# ionode.net
KiCad netlist of a schematic drawn in EAGLE
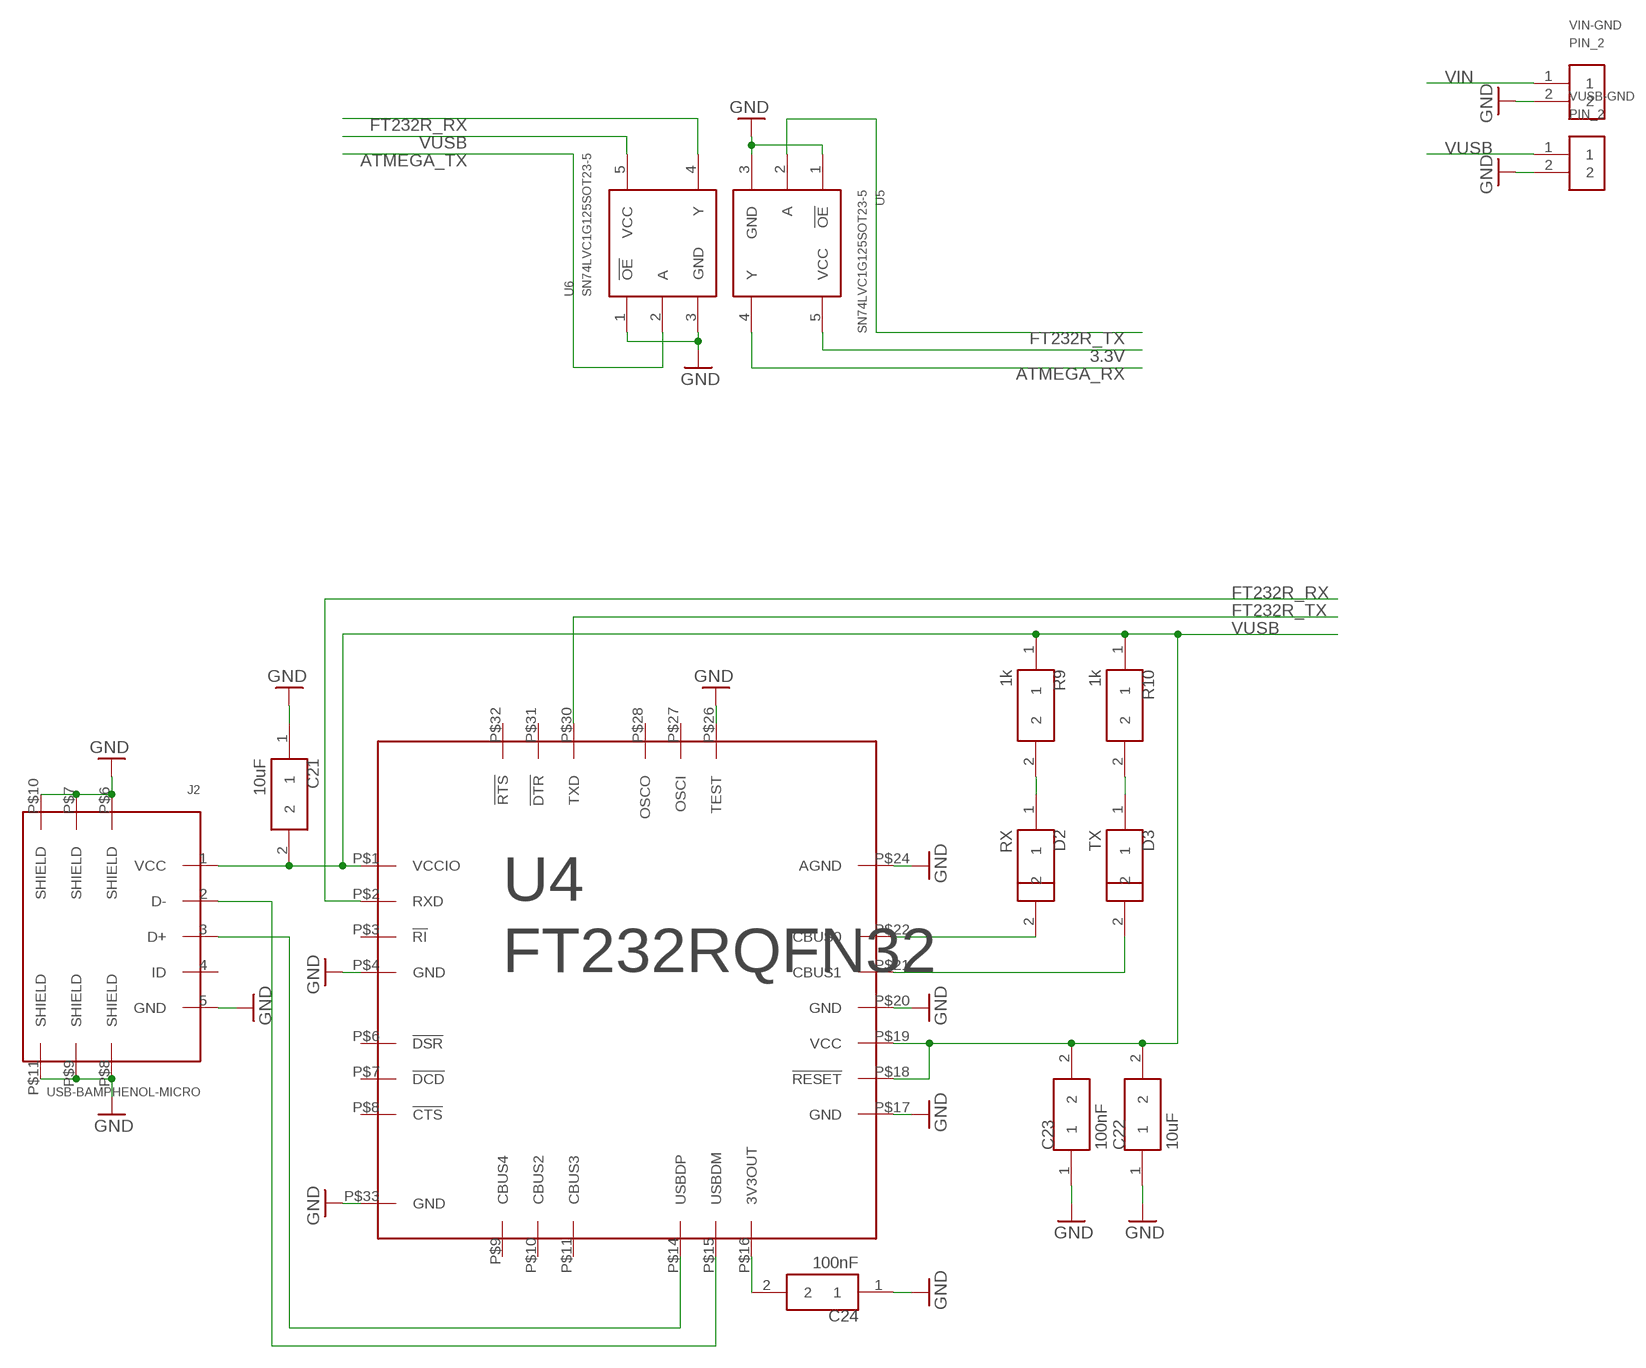
[diagram p0: schematic, sheet 1, part 1 of 2]
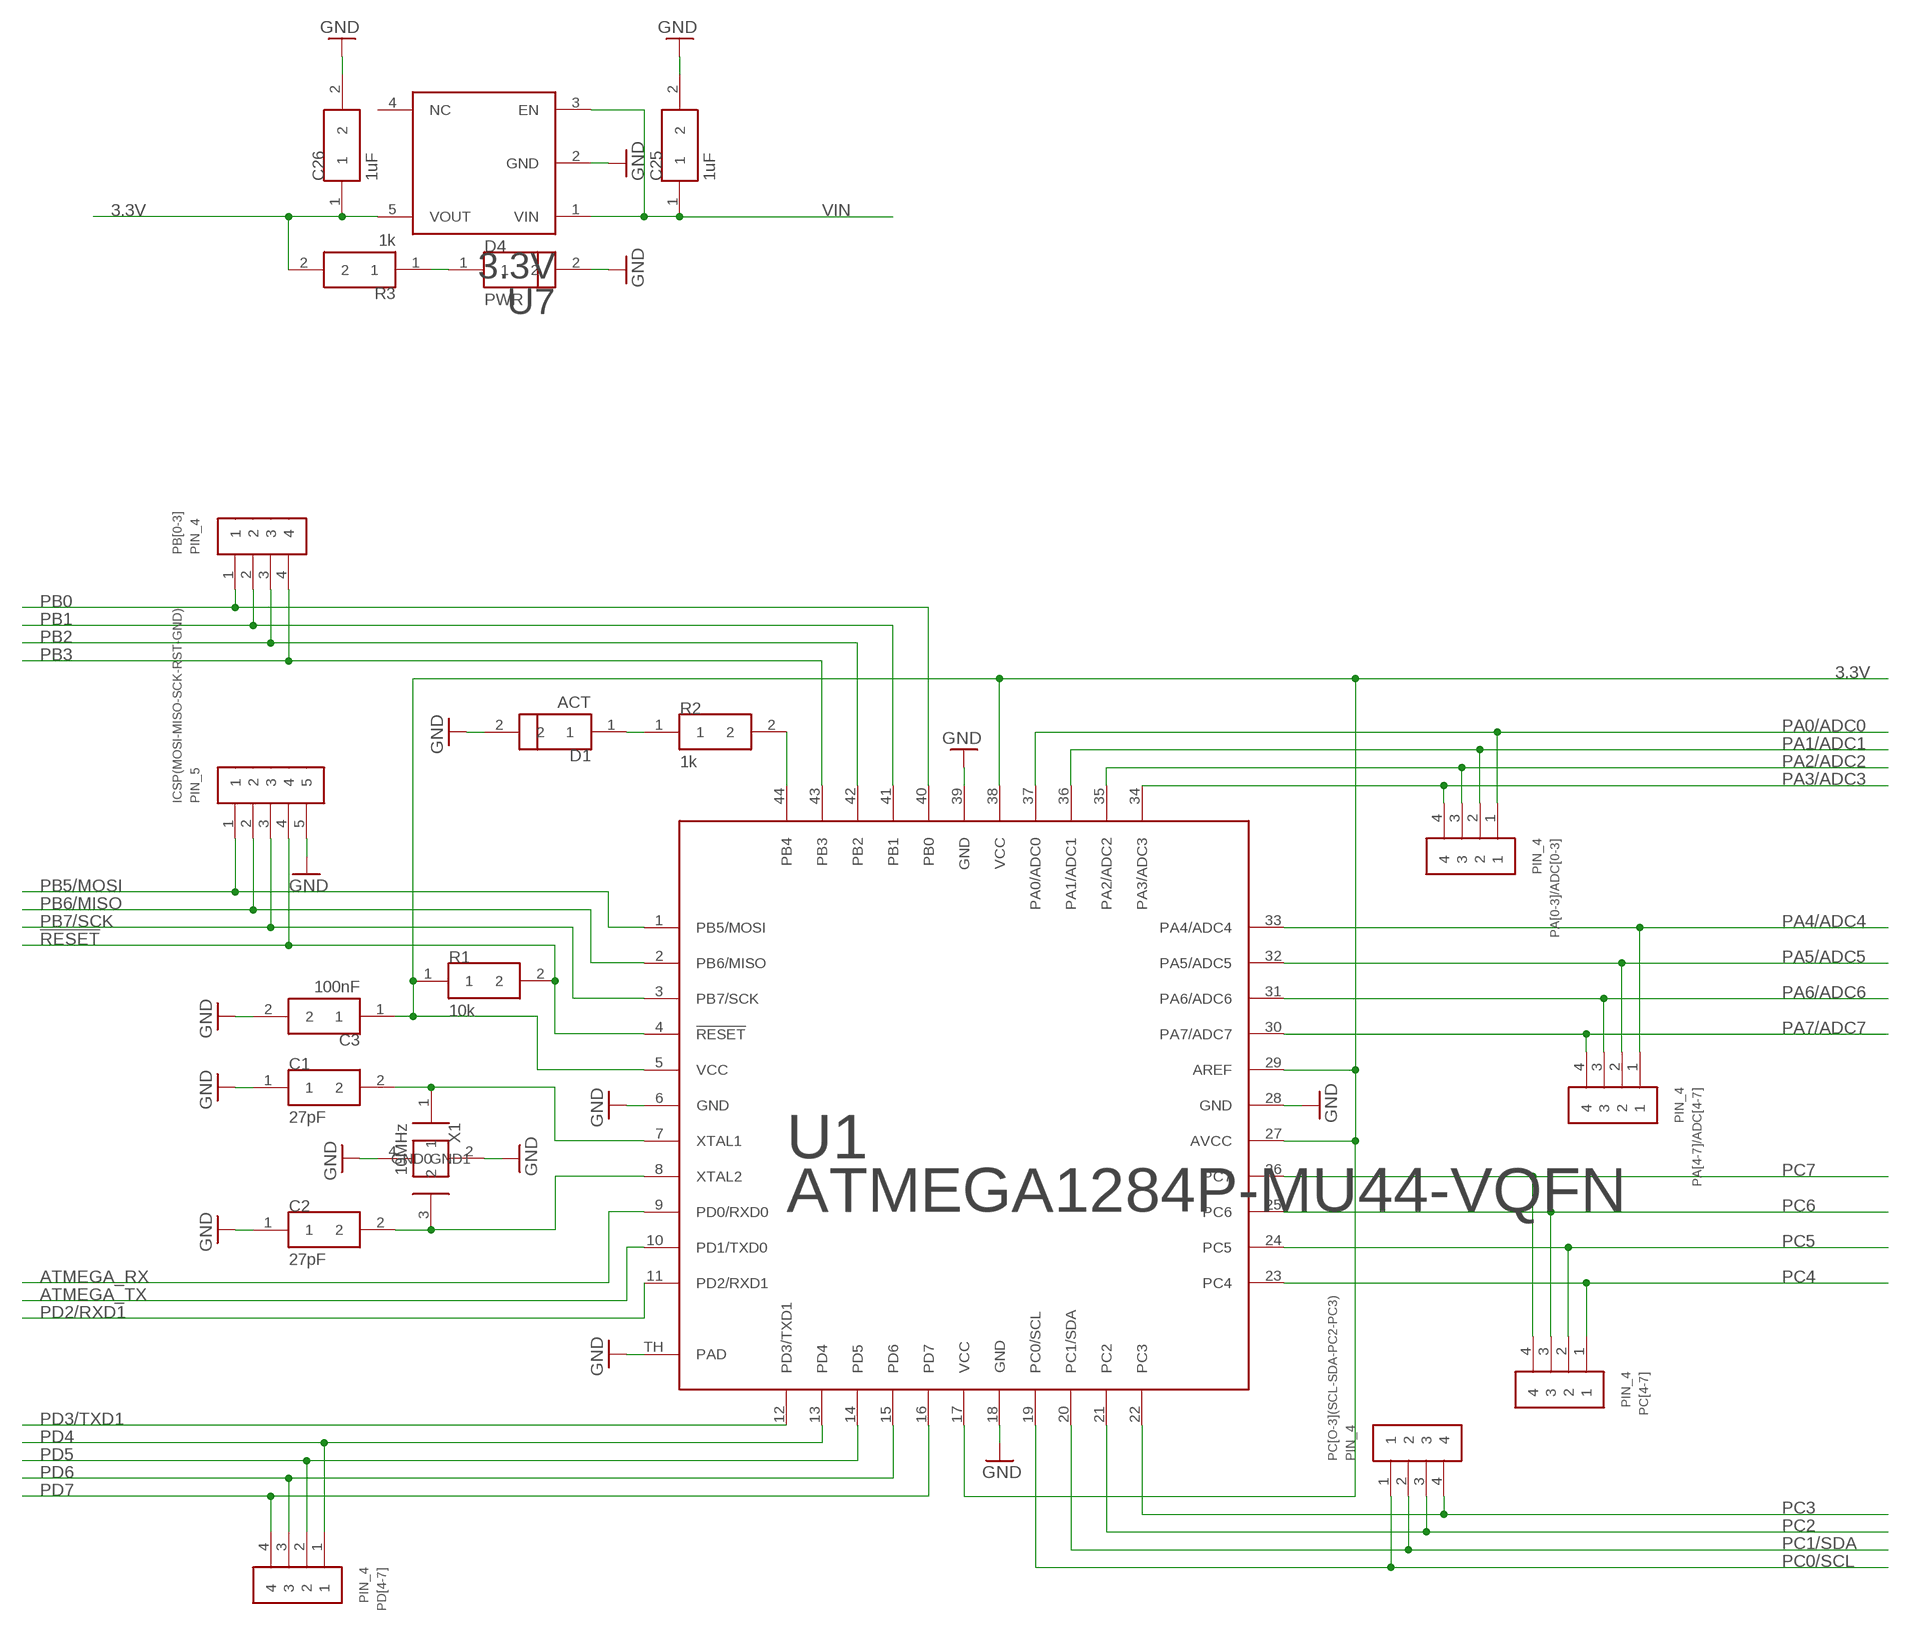
[diagram p1: schematic, sheet 1, part 2 of 2]

(export (version "E")
  (design (tool "Eeschema 10.0.6"))
  (components
    (comp (ref "C1")
      (value "27pF")
      (footprint "eagle-import:0805")
      (libsource (lib "eagle-import") (part "CAP0805"))
    )
    (comp (ref "C2")
      (value "27pF")
      (footprint "eagle-import:0805")
      (libsource (lib "eagle-import") (part "CAP0805"))
    )
    (comp (ref "C3")
      (value "100nF")
      (footprint "eagle-import:0805")
      (libsource (lib "eagle-import") (part "CAP0805"))
    )
    (comp (ref "C21")
      (value "10uF")
      (footprint "eagle-import:0805")
      (libsource (lib "eagle-import") (part "CAP0805"))
    )
    (comp (ref "C22")
      (value "10uF")
      (footprint "eagle-import:0805")
      (libsource (lib "eagle-import") (part "CAP0805"))
    )
    (comp (ref "C23")
      (value "100nF")
      (footprint "eagle-import:0805")
      (libsource (lib "eagle-import") (part "CAP0805"))
    )
    (comp (ref "C24")
      (value "100nF")
      (footprint "eagle-import:0805")
      (libsource (lib "eagle-import") (part "CAP0805"))
    )
    (comp (ref "C25")
      (value "1uF")
      (footprint "eagle-import:0805")
      (libsource (lib "eagle-import") (part "CAP0805"))
    )
    (comp (ref "C26")
      (value "1uF")
      (footprint "eagle-import:0805")
      (libsource (lib "eagle-import") (part "CAP0805"))
    )
    (comp (ref "D1")
      (value "ACT")
      (footprint "eagle-import:0805")
      (libsource (lib "eagle-import") (part "LED0805"))
    )
    (comp (ref "D2")
      (value "RX")
      (footprint "eagle-import:0805")
      (libsource (lib "eagle-import") (part "LED0805"))
    )
    (comp (ref "D3")
      (value "TX")
      (footprint "eagle-import:0805")
      (libsource (lib "eagle-import") (part "LED0805"))
    )
    (comp (ref "D4")
      (value "PWR")
      (footprint "eagle-import:0805")
      (libsource (lib "eagle-import") (part "LED0805"))
    )
    (comp (ref "ICSP(MOSI-MISO-SCK-RST-GND)")
      (value "PIN_5")
      (footprint "eagle-import:PIN_5")
      (libsource (lib "eagle-import") (part "PIN_5"))
    )
    (comp (ref "J2")
      (value "USB-BAMPHENOL-MICRO")
      (footprint "eagle-import:AMPHENOL-USB-MICRO-B")
      (libsource (lib "eagle-import") (part "USB-BAMPHENOL-MICRO"))
    )
    (comp (ref "PA[0-3]/ADC[0-3]")
      (value "PIN_4")
      (footprint "eagle-import:PIN_4")
      (libsource (lib "eagle-import") (part "PIN_4"))
    )
    (comp (ref "PA[4-7]/ADC[4-7]")
      (value "PIN_4")
      (footprint "eagle-import:PIN_4")
      (libsource (lib "eagle-import") (part "PIN_4"))
    )
    (comp (ref "PB[0-3]")
      (value "PIN_4")
      (footprint "eagle-import:PIN_4")
      (libsource (lib "eagle-import") (part "PIN_4"))
    )
    (comp (ref "PC[4-7]")
      (value "PIN_4")
      (footprint "eagle-import:PIN_4")
      (libsource (lib "eagle-import") (part "PIN_4"))
    )
    (comp (ref "PC[O-3](SCL-SDA-PC2-PC3)")
      (value "PIN_4")
      (footprint "eagle-import:PIN_4")
      (libsource (lib "eagle-import") (part "PIN_4"))
    )
    (comp (ref "PD[4-7]")
      (value "PIN_4")
      (footprint "eagle-import:PIN_4")
      (libsource (lib "eagle-import") (part "PIN_4"))
    )
    (comp (ref "R1")
      (value "10k")
      (footprint "eagle-import:0805")
      (libsource (lib "eagle-import") (part "RES0805"))
    )
    (comp (ref "R2")
      (value "1k")
      (footprint "eagle-import:0805")
      (libsource (lib "eagle-import") (part "RES0805"))
    )
    (comp (ref "R3")
      (value "1k")
      (footprint "eagle-import:0805")
      (libsource (lib "eagle-import") (part "RES0805"))
    )
    (comp (ref "R9")
      (value "1k")
      (footprint "eagle-import:0805")
      (libsource (lib "eagle-import") (part "RES0805"))
    )
    (comp (ref "R10")
      (value "1k")
      (footprint "eagle-import:0805")
      (libsource (lib "eagle-import") (part "RES0805"))
    )
    (comp (ref "U1")
      (value "ATMEGA1284P-MU44-VQFN")
      (footprint "eagle-import:44-VQFN")
      (libsource (lib "eagle-import") (part "ATMEGA1284P-MU44-VQFN"))
    )
    (comp (ref "U4")
      (value "FT232RQFN32")
      (footprint "eagle-import:32-VQFN")
      (libsource (lib "eagle-import") (part "FT232RQFN32"))
    )
    (comp (ref "U5")
      (value "SN74LVC1G125SOT23-5")
      (footprint "eagle-import:SOT23-5")
      (libsource (lib "eagle-import") (part "SN74LVC1G125SOT23-5"))
    )
    (comp (ref "U6")
      (value "SN74LVC1G125SOT23-5")
      (footprint "eagle-import:SOT23-5")
      (libsource (lib "eagle-import") (part "SN74LVC1G125SOT23-5"))
    )
    (comp (ref "U7")
      (value "3.3V")
      (footprint "eagle-import:SOT23-5")
      (libsource (lib "eagle-import") (part "LP3985SOT23-5"))
    )
    (comp (ref "VIN-GND")
      (value "PIN_2")
      (footprint "eagle-import:PIN_2")
      (libsource (lib "eagle-import") (part "PIN_2"))
    )
    (comp (ref "VUSB-GND")
      (value "PIN_2")
      (footprint "eagle-import:PIN_2")
      (libsource (lib "eagle-import") (part "PIN_2"))
    )
    (comp (ref "X1")
      (value "10MHz")
      (footprint "eagle-import:XTAL_3225")
      (libsource (lib "eagle-import") (part "XTAL_GNDSMD_3225"))
    )
  )
  (nets
    (net (code "1") (name "/3.3V") (class "Default")
      (node (ref "C26") (pin "1") (pinfunction "1_1") (pintype "bidirectional"))
      (node (ref "C3") (pin "1") (pinfunction "1_1") (pintype "bidirectional"))
      (node (ref "R1") (pin "1") (pinfunction "1_1") (pintype "bidirectional"))
      (node (ref "R3") (pin "2") (pinfunction "2_2") (pintype "bidirectional"))
      (node (ref "U1") (pin "17") (pinfunction "VCC_17") (pintype "bidirectional"))
      (node (ref "U1") (pin "27") (pinfunction "AVCC_27") (pintype "bidirectional"))
      (node (ref "U1") (pin "29") (pinfunction "AREF_29") (pintype "bidirectional"))
      (node (ref "U1") (pin "38") (pinfunction "VCC_38") (pintype "bidirectional"))
      (node (ref "U1") (pin "5") (pinfunction "VCC_5") (pintype "bidirectional"))
      (node (ref "U5") (pin "5") (pinfunction "VCC_5") (pintype "bidirectional"))
      (node (ref "U7") (pin "5") (pinfunction "VOUT_5") (pintype "bidirectional"))
    )
    (net (code "2") (name "/ATMEGA_RX") (class "Default")
      (node (ref "U1") (pin "9") (pinfunction "PD0/RXD0_9") (pintype "bidirectional"))
      (node (ref "U5") (pin "4") (pinfunction "Y_4") (pintype "bidirectional"))
    )
    (net (code "3") (name "/ATMEGA_TX") (class "Default")
      (node (ref "U1") (pin "10") (pinfunction "PD1/TXD0_10") (pintype "bidirectional"))
      (node (ref "U6") (pin "2") (pinfunction "A_2") (pintype "bidirectional"))
    )
    (net (code "4") (name "/FT232R_RX") (class "Default")
      (node (ref "U4") (pin "P$2") (pinfunction "RXD_P$2") (pintype "bidirectional"))
      (node (ref "U6") (pin "4") (pinfunction "Y_4") (pintype "bidirectional"))
    )
    (net (code "5") (name "/FT232R_TX") (class "Default")
      (node (ref "U4") (pin "P$30") (pinfunction "TXD_P$30") (pintype "bidirectional"))
      (node (ref "U5") (pin "2") (pinfunction "A_2") (pintype "bidirectional"))
    )
    (net (code "6") (name "/PA0{slash}ADC0") (class "Default")
      (node (ref "PA[0-3]/ADC[0-3]") (pin "1") (pinfunction "1_1") (pintype "bidirectional"))
      (node (ref "U1") (pin "37") (pinfunction "PA0/ADC0_37") (pintype "bidirectional"))
    )
    (net (code "7") (name "/PA1{slash}ADC1") (class "Default")
      (node (ref "PA[0-3]/ADC[0-3]") (pin "2") (pinfunction "2_2") (pintype "bidirectional"))
      (node (ref "U1") (pin "36") (pinfunction "PA1/ADC1_36") (pintype "bidirectional"))
    )
    (net (code "8") (name "/PA2{slash}ADC2") (class "Default")
      (node (ref "PA[0-3]/ADC[0-3]") (pin "3") (pinfunction "3_3") (pintype "bidirectional"))
      (node (ref "U1") (pin "35") (pinfunction "PA2/ADC2_35") (pintype "bidirectional"))
    )
    (net (code "9") (name "/PA3{slash}ADC3") (class "Default")
      (node (ref "PA[0-3]/ADC[0-3]") (pin "4") (pinfunction "4_4") (pintype "bidirectional"))
      (node (ref "U1") (pin "34") (pinfunction "PA3/ADC3_34") (pintype "bidirectional"))
    )
    (net (code "10") (name "/PA4{slash}ADC4") (class "Default")
      (node (ref "PA[4-7]/ADC[4-7]") (pin "1") (pinfunction "1_1") (pintype "bidirectional"))
      (node (ref "U1") (pin "33") (pinfunction "PA4/ADC4_33") (pintype "bidirectional"))
    )
    (net (code "11") (name "/PA5{slash}ADC5") (class "Default")
      (node (ref "PA[4-7]/ADC[4-7]") (pin "2") (pinfunction "2_2") (pintype "bidirectional"))
      (node (ref "U1") (pin "32") (pinfunction "PA5/ADC5_32") (pintype "bidirectional"))
    )
    (net (code "12") (name "/PA6{slash}ADC6") (class "Default")
      (node (ref "PA[4-7]/ADC[4-7]") (pin "3") (pinfunction "3_3") (pintype "bidirectional"))
      (node (ref "U1") (pin "31") (pinfunction "PA6/ADC6_31") (pintype "bidirectional"))
    )
    (net (code "13") (name "/PA7{slash}ADC7") (class "Default")
      (node (ref "PA[4-7]/ADC[4-7]") (pin "4") (pinfunction "4_4") (pintype "bidirectional"))
      (node (ref "U1") (pin "30") (pinfunction "PA7/ADC7_30") (pintype "bidirectional"))
    )
    (net (code "14") (name "/PB0") (class "Default")
      (node (ref "PB[0-3]") (pin "1") (pinfunction "1_1") (pintype "bidirectional"))
      (node (ref "U1") (pin "40") (pinfunction "PB0_40") (pintype "bidirectional"))
    )
    (net (code "15") (name "/PB1") (class "Default")
      (node (ref "PB[0-3]") (pin "2") (pinfunction "2_2") (pintype "bidirectional"))
      (node (ref "U1") (pin "41") (pinfunction "PB1_41") (pintype "bidirectional"))
    )
    (net (code "16") (name "/PB2") (class "Default")
      (node (ref "PB[0-3]") (pin "3") (pinfunction "3_3") (pintype "bidirectional"))
      (node (ref "U1") (pin "42") (pinfunction "PB2_42") (pintype "bidirectional"))
    )
    (net (code "17") (name "/PB3") (class "Default")
      (node (ref "PB[0-3]") (pin "4") (pinfunction "4_4") (pintype "bidirectional"))
      (node (ref "U1") (pin "43") (pinfunction "PB3_43") (pintype "bidirectional"))
    )
    (net (code "18") (name "/PB5{slash}MOSI") (class "Default")
      (node (ref "ICSP(MOSI-MISO-SCK-RST-GND)") (pin "1") (pinfunction "1_1") (pintype "bidirectional"))
      (node (ref "U1") (pin "1") (pinfunction "PB5/MOSI_1") (pintype "bidirectional"))
    )
    (net (code "19") (name "/PB6{slash}MISO") (class "Default")
      (node (ref "ICSP(MOSI-MISO-SCK-RST-GND)") (pin "2") (pinfunction "2_2") (pintype "bidirectional"))
      (node (ref "U1") (pin "2") (pinfunction "PB6/MISO_2") (pintype "bidirectional"))
    )
    (net (code "20") (name "/PB7{slash}SCK") (class "Default")
      (node (ref "ICSP(MOSI-MISO-SCK-RST-GND)") (pin "3") (pinfunction "3_3") (pintype "bidirectional"))
      (node (ref "U1") (pin "3") (pinfunction "PB7/SCK_3") (pintype "bidirectional"))
    )
    (net (code "21") (name "/PC0{slash}SCL") (class "Default")
      (node (ref "PC[O-3](SCL-SDA-PC2-PC3)") (pin "1") (pinfunction "1_1") (pintype "bidirectional"))
      (node (ref "U1") (pin "19") (pinfunction "PC0/SCL_19") (pintype "bidirectional"))
    )
    (net (code "22") (name "/PC1{slash}SDA") (class "Default")
      (node (ref "PC[O-3](SCL-SDA-PC2-PC3)") (pin "2") (pinfunction "2_2") (pintype "bidirectional"))
      (node (ref "U1") (pin "20") (pinfunction "PC1/SDA_20") (pintype "bidirectional"))
    )
    (net (code "23") (name "/PC2") (class "Default")
      (node (ref "PC[O-3](SCL-SDA-PC2-PC3)") (pin "3") (pinfunction "3_3") (pintype "bidirectional"))
      (node (ref "U1") (pin "21") (pinfunction "PC2_21") (pintype "bidirectional"))
    )
    (net (code "24") (name "/PC3") (class "Default")
      (node (ref "PC[O-3](SCL-SDA-PC2-PC3)") (pin "4") (pinfunction "4_4") (pintype "bidirectional"))
      (node (ref "U1") (pin "22") (pinfunction "PC3_22") (pintype "bidirectional"))
    )
    (net (code "25") (name "/PC4") (class "Default")
      (node (ref "PC[4-7]") (pin "1") (pinfunction "1_1") (pintype "bidirectional"))
      (node (ref "U1") (pin "23") (pinfunction "PC4_23") (pintype "bidirectional"))
    )
    (net (code "26") (name "/PC5") (class "Default")
      (node (ref "PC[4-7]") (pin "2") (pinfunction "2_2") (pintype "bidirectional"))
      (node (ref "U1") (pin "24") (pinfunction "PC5_24") (pintype "bidirectional"))
    )
    (net (code "27") (name "/PC6") (class "Default")
      (node (ref "PC[4-7]") (pin "3") (pinfunction "3_3") (pintype "bidirectional"))
      (node (ref "U1") (pin "25") (pinfunction "PC6_25") (pintype "bidirectional"))
    )
    (net (code "28") (name "/PC7") (class "Default")
      (node (ref "PC[4-7]") (pin "4") (pinfunction "4_4") (pintype "bidirectional"))
      (node (ref "U1") (pin "26") (pinfunction "PC7_26") (pintype "bidirectional"))
    )
    (net (code "29") (name "/PD2{slash}RXD1") (class "Default")
      (node (ref "U1") (pin "11") (pinfunction "PD2/RXD1_11") (pintype "bidirectional"))
    )
    (net (code "30") (name "/PD3{slash}TXD1") (class "Default")
      (node (ref "U1") (pin "12") (pinfunction "PD3/TXD1_12") (pintype "bidirectional"))
    )
    (net (code "31") (name "/PD4") (class "Default")
      (node (ref "PD[4-7]") (pin "1") (pinfunction "1_1") (pintype "bidirectional"))
      (node (ref "U1") (pin "13") (pinfunction "PD4_13") (pintype "bidirectional"))
    )
    (net (code "32") (name "/PD5") (class "Default")
      (node (ref "PD[4-7]") (pin "2") (pinfunction "2_2") (pintype "bidirectional"))
      (node (ref "U1") (pin "14") (pinfunction "PD5_14") (pintype "bidirectional"))
    )
    (net (code "33") (name "/PD6") (class "Default")
      (node (ref "PD[4-7]") (pin "3") (pinfunction "3_3") (pintype "bidirectional"))
      (node (ref "U1") (pin "15") (pinfunction "PD6_15") (pintype "bidirectional"))
    )
    (net (code "34") (name "/PD7") (class "Default")
      (node (ref "PD[4-7]") (pin "4") (pinfunction "4_4") (pintype "bidirectional"))
      (node (ref "U1") (pin "16") (pinfunction "PD7_16") (pintype "bidirectional"))
    )
    (net (code "35") (name "/VIN") (class "Default")
      (node (ref "C25") (pin "1") (pinfunction "1_1") (pintype "bidirectional"))
      (node (ref "U7") (pin "1") (pinfunction "VIN_1") (pintype "bidirectional"))
      (node (ref "U7") (pin "3") (pinfunction "EN_3") (pintype "bidirectional"))
      (node (ref "VIN-GND") (pin "1") (pinfunction "1_1") (pintype "bidirectional"))
    )
    (net (code "36") (name "/VUSB") (class "Default")
      (node (ref "C21") (pin "2") (pinfunction "2_2") (pintype "bidirectional"))
      (node (ref "C22") (pin "2") (pinfunction "2_2") (pintype "bidirectional"))
      (node (ref "C23") (pin "2") (pinfunction "2_2") (pintype "bidirectional"))
      (node (ref "J2") (pin "1") (pinfunction "VCC_1") (pintype "bidirectional"))
      (node (ref "R10") (pin "1") (pinfunction "1_1") (pintype "bidirectional"))
      (node (ref "R9") (pin "1") (pinfunction "1_1") (pintype "bidirectional"))
      (node (ref "U4") (pin "P$1") (pinfunction "VCCIO_P$1") (pintype "bidirectional"))
      (node (ref "U4") (pin "P$18") (pinfunction "~{RESET}_P$18") (pintype "bidirectional"))
      (node (ref "U4") (pin "P$19") (pinfunction "VCC_P$19") (pintype "bidirectional"))
      (node (ref "U6") (pin "5") (pinfunction "VCC_5") (pintype "bidirectional"))
      (node (ref "VUSB-GND") (pin "1") (pinfunction "1_1") (pintype "bidirectional"))
    )
    (net (code "37") (name "/~{RESET}") (class "Default")
      (node (ref "ICSP(MOSI-MISO-SCK-RST-GND)") (pin "4") (pinfunction "4_4") (pintype "bidirectional"))
      (node (ref "R1") (pin "2") (pinfunction "2_2") (pintype "bidirectional"))
      (node (ref "U1") (pin "4") (pinfunction "~{RESET}_4") (pintype "bidirectional"))
    )
    (net (code "38") (name "GND") (class "Default")
      (node (ref "C1") (pin "1") (pinfunction "1_1") (pintype "bidirectional"))
      (node (ref "C2") (pin "1") (pinfunction "1_1") (pintype "bidirectional"))
      (node (ref "C21") (pin "1") (pinfunction "1_1") (pintype "bidirectional"))
      (node (ref "C22") (pin "1") (pinfunction "1_1") (pintype "bidirectional"))
      (node (ref "C23") (pin "1") (pinfunction "1_1") (pintype "bidirectional"))
      (node (ref "C24") (pin "1") (pinfunction "1_1") (pintype "bidirectional"))
      (node (ref "C25") (pin "2") (pinfunction "2_2") (pintype "bidirectional"))
      (node (ref "C26") (pin "2") (pinfunction "2_2") (pintype "bidirectional"))
      (node (ref "C3") (pin "2") (pinfunction "2_2") (pintype "bidirectional"))
      (node (ref "D1") (pin "2") (pinfunction "2_2") (pintype "bidirectional"))
      (node (ref "D4") (pin "2") (pinfunction "2_2") (pintype "bidirectional"))
      (node (ref "ICSP(MOSI-MISO-SCK-RST-GND)") (pin "5") (pinfunction "5_5") (pintype "bidirectional"))
      (node (ref "J2") (pin "5") (pinfunction "GND_5") (pintype "bidirectional"))
      (node (ref "J2") (pin "P$10") (pinfunction "SHIELD_P$10") (pintype "bidirectional"))
      (node (ref "J2") (pin "P$11") (pinfunction "SHIELD_P$11") (pintype "bidirectional"))
      (node (ref "J2") (pin "P$6") (pinfunction "SHIELD_P$6") (pintype "bidirectional"))
      (node (ref "J2") (pin "P$7") (pinfunction "SHIELD_P$7") (pintype "bidirectional"))
      (node (ref "J2") (pin "P$8") (pinfunction "SHIELD_P$8") (pintype "bidirectional"))
      (node (ref "J2") (pin "P$9") (pinfunction "SHIELD_P$9") (pintype "bidirectional"))
      (node (ref "U1") (pin "18") (pinfunction "GND_18") (pintype "bidirectional"))
      (node (ref "U1") (pin "28") (pinfunction "GND_28") (pintype "bidirectional"))
      (node (ref "U1") (pin "39") (pinfunction "GND_39") (pintype "bidirectional"))
      (node (ref "U1") (pin "6") (pinfunction "GND_6") (pintype "bidirectional"))
      (node (ref "U1") (pin "TH") (pinfunction "PAD_TH") (pintype "bidirectional"))
      (node (ref "U4") (pin "P$17") (pinfunction "GND_P$17") (pintype "bidirectional"))
      (node (ref "U4") (pin "P$20") (pinfunction "GND_P$20") (pintype "bidirectional"))
      (node (ref "U4") (pin "P$24") (pinfunction "AGND_P$24") (pintype "bidirectional"))
      (node (ref "U4") (pin "P$26") (pinfunction "TEST_P$26") (pintype "bidirectional"))
      (node (ref "U4") (pin "P$33") (pinfunction "GND_P$33") (pintype "bidirectional"))
      (node (ref "U4") (pin "P$4") (pinfunction "GND_P$4") (pintype "bidirectional"))
      (node (ref "U5") (pin "1") (pinfunction "~{OE}_1") (pintype "bidirectional"))
      (node (ref "U5") (pin "3") (pinfunction "GND_3") (pintype "bidirectional"))
      (node (ref "U6") (pin "1") (pinfunction "~{OE}_1") (pintype "bidirectional"))
      (node (ref "U6") (pin "3") (pinfunction "GND_3") (pintype "bidirectional"))
      (node (ref "U7") (pin "2") (pinfunction "GND_2") (pintype "bidirectional"))
      (node (ref "VIN-GND") (pin "2") (pinfunction "2_2") (pintype "bidirectional"))
      (node (ref "VUSB-GND") (pin "2") (pinfunction "2_2") (pintype "bidirectional"))
      (node (ref "X1") (pin "2") (pinfunction "GND0_2") (pintype "bidirectional"))
      (node (ref "X1") (pin "4") (pinfunction "GND1_4") (pintype "bidirectional"))
    )
    (net (code "39") (name "Net-(D1-Pad1)") (class "Default")
      (node (ref "D1") (pin "1") (pinfunction "1_1") (pintype "bidirectional"))
      (node (ref "R2") (pin "1") (pinfunction "1_1") (pintype "bidirectional"))
    )
    (net (code "40") (name "Net-(D2-Pad1)") (class "Default")
      (node (ref "D2") (pin "1") (pinfunction "1_1") (pintype "bidirectional"))
      (node (ref "R9") (pin "2") (pinfunction "2_2") (pintype "bidirectional"))
    )
    (net (code "41") (name "Net-(D3-Pad1)") (class "Default")
      (node (ref "D3") (pin "1") (pinfunction "1_1") (pintype "bidirectional"))
      (node (ref "R10") (pin "2") (pinfunction "2_2") (pintype "bidirectional"))
    )
    (net (code "42") (name "Net-(D4-Pad1)") (class "Default")
      (node (ref "D4") (pin "1") (pinfunction "1_1") (pintype "bidirectional"))
      (node (ref "R3") (pin "1") (pinfunction "1_1") (pintype "bidirectional"))
    )
    (net (code "43") (name "Net-(J2-D+)") (class "Default")
      (node (ref "J2") (pin "3") (pinfunction "D+_3") (pintype "bidirectional"))
      (node (ref "U4") (pin "P$14") (pinfunction "USBDP_P$14") (pintype "bidirectional"))
    )
    (net (code "44") (name "Net-(J2-D-)") (class "Default")
      (node (ref "J2") (pin "2") (pinfunction "D-_2") (pintype "bidirectional"))
      (node (ref "U4") (pin "P$15") (pinfunction "USBDM_P$15") (pintype "bidirectional"))
    )
    (net (code "45") (name "Net-(U1-PB4)") (class "Default")
      (node (ref "R2") (pin "2") (pinfunction "2_2") (pintype "bidirectional"))
      (node (ref "U1") (pin "44") (pinfunction "PB4_44") (pintype "bidirectional"))
    )
    (net (code "46") (name "Net-(U1-XTAL1)") (class "Default")
      (node (ref "C1") (pin "2") (pinfunction "2_2") (pintype "bidirectional"))
      (node (ref "U1") (pin "7") (pinfunction "XTAL1_7") (pintype "bidirectional"))
      (node (ref "X1") (pin "1") (pinfunction "1_1") (pintype "bidirectional"))
    )
    (net (code "47") (name "Net-(U1-XTAL2)") (class "Default")
      (node (ref "C2") (pin "2") (pinfunction "2_2") (pintype "bidirectional"))
      (node (ref "U1") (pin "8") (pinfunction "XTAL2_8") (pintype "bidirectional"))
      (node (ref "X1") (pin "3") (pinfunction "2_3") (pintype "bidirectional"))
    )
    (net (code "48") (name "Net-(U4-3V3OUT)") (class "Default")
      (node (ref "C24") (pin "2") (pinfunction "2_2") (pintype "bidirectional"))
      (node (ref "U4") (pin "P$16") (pinfunction "3V3OUT_P$16") (pintype "bidirectional"))
    )
    (net (code "49") (name "Net-(U4-CBUS0)") (class "Default")
      (node (ref "D2") (pin "2") (pinfunction "2_2") (pintype "bidirectional"))
      (node (ref "U4") (pin "P$22") (pinfunction "CBUS0_P$22") (pintype "bidirectional"))
    )
    (net (code "50") (name "Net-(U4-CBUS1)") (class "Default")
      (node (ref "D3") (pin "2") (pinfunction "2_2") (pintype "bidirectional"))
      (node (ref "U4") (pin "P$21") (pinfunction "CBUS1_P$21") (pintype "bidirectional"))
    )
    (net (code "51") (name "unconnected-(J2-ID-Pad4)") (class "Default")
      (node (ref "J2") (pin "4") (pinfunction "ID_4") (pintype "bidirectional"))
    )
    (net (code "52") (name "unconnected-(U4-CBUS2-PadP$10)") (class "Default")
      (node (ref "U4") (pin "P$10") (pinfunction "CBUS2_P$10") (pintype "bidirectional"))
    )
    (net (code "53") (name "unconnected-(U4-CBUS3-PadP$11)") (class "Default")
      (node (ref "U4") (pin "P$11") (pinfunction "CBUS3_P$11") (pintype "bidirectional"))
    )
    (net (code "54") (name "unconnected-(U4-CBUS4-PadP$9)") (class "Default")
      (node (ref "U4") (pin "P$9") (pinfunction "CBUS4_P$9") (pintype "bidirectional"))
    )
    (net (code "55") (name "unconnected-(U4-OSCI-PadP$27)") (class "Default")
      (node (ref "U4") (pin "P$27") (pinfunction "OSCI_P$27") (pintype "bidirectional"))
    )
    (net (code "56") (name "unconnected-(U4-OSCO-PadP$28)") (class "Default")
      (node (ref "U4") (pin "P$28") (pinfunction "OSCO_P$28") (pintype "bidirectional"))
    )
    (net (code "57") (name "unconnected-(U4-~{CTS}-PadP$8)") (class "Default")
      (node (ref "U4") (pin "P$8") (pinfunction "~{CTS}_P$8") (pintype "bidirectional"))
    )
    (net (code "58") (name "unconnected-(U4-~{DCD}-PadP$7)") (class "Default")
      (node (ref "U4") (pin "P$7") (pinfunction "~{DCD}_P$7") (pintype "bidirectional"))
    )
    (net (code "59") (name "unconnected-(U4-~{DSR}-PadP$6)") (class "Default")
      (node (ref "U4") (pin "P$6") (pinfunction "~{DSR}_P$6") (pintype "bidirectional"))
    )
    (net (code "60") (name "unconnected-(U4-~{DTR}-PadP$31)") (class "Default")
      (node (ref "U4") (pin "P$31") (pinfunction "~{DTR}_P$31") (pintype "bidirectional"))
    )
    (net (code "61") (name "unconnected-(U4-~{RI}-PadP$3)") (class "Default")
      (node (ref "U4") (pin "P$3") (pinfunction "~{RI}_P$3") (pintype "bidirectional"))
    )
    (net (code "62") (name "unconnected-(U4-~{RTS}-PadP$32)") (class "Default")
      (node (ref "U4") (pin "P$32") (pinfunction "~{RTS}_P$32") (pintype "bidirectional"))
    )
    (net (code "63") (name "unconnected-(U7-NC-Pad4)") (class "Default")
      (node (ref "U7") (pin "4") (pinfunction "NC_4") (pintype "bidirectional"))
    )
  )
)
